# Sheet_Power.net
KiCad netlist of a schematic drawn in Altium Designer
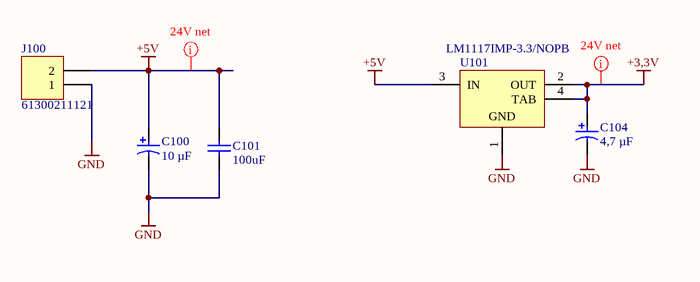
[diagram p0: Sheet_Power.SchDoc]

(export (version "E")
  (design (tool "Eeschema 10.0.6"))
  (components
    (comp (ref "C100")
      (value "10 µF")
      (footprint "KEMT-520-D_Low")
      (description "10 µF, 35V, 125 mOhm, Gr. D\npartnumb: T495D106K035ATE125")
      (fields (field (name "MANUFACTURER") "KEMET") (field (name "TOLERANCE") "±10%"))
      (libsource (lib "Altium Vault EMBL") (part "CMP-001-0033-3"))
    )
    (comp (ref "C101")
      (value "100uF")
      (footprint "CAPC1206(3216)190_L")
      (description "CAP 100uF 6.3V ±20% 1206 (3216 Metric) Thickness 1.9mm SMD")
      (fields (field (name "TOLERANCE") "Â±20%") (field (name "PARTNUMBER") "885012108005"))
      (libsource (lib "Altium Vault EMBL 3") (part "CMP-00469-2"))
    )
    (comp (ref "C104")
      (value "4,7 µF")
      (footprint "A Package")
      (description "4,7 µF; 6V; Gr. A; T491A475K006AT")
      (fields (field (name "MANUFACTURER") "KEMET") (field (name "TOLERANCE") "±10%"))
      (libsource (lib "Altium Vault EMBL") (part "CMP-001-0039-3"))
    )
    (comp (ref "J100")
      (value "61300211121")
      (footprint "61300211121")
      (description "2Pol; gerade; WR-PHD 2.54 mm THT Pin Header")
      (fields (field (name "MANUFACTURER") "Wurth Electronics"))
      (libsource (lib "Altium Vault EMBL") (part "CMP-001-0071-1"))
    )
    (comp (ref "U101")
      (value "LM1117IMP-3.3/NOPB")
      (footprint "DCY0004A_N")
      (description "800mA Low-Dropout Linear Regulator, 4-pin SOT-223, Pb-Free")
      (fields (field (name "MANUFACTURER") "Texas Instruments"))
      (libsource (lib "Altium Vault EMBL") (part "CMP-00484-1"))
    )
  )
  (nets
    (net (code "1") (name "+3,3V") (class "Default")
      (node (ref "C104") (pin "1") (pinfunction "1_1") (pintype "passive"))
      (node (ref "U101") (pin "2") (pinfunction "OUT_2") (pintype "power_in"))
      (node (ref "U101") (pin "4") (pinfunction "TAB_4") (pintype "power_in"))
    )
    (net (code "2") (name "+5V") (class "Default")
      (node (ref "C100") (pin "1") (pinfunction "1_1") (pintype "passive"))
      (node (ref "C101") (pin "2") (pinfunction "2_2") (pintype "passive"))
      (node (ref "J100") (pin "2") (pinfunction "2_2") (pintype "passive"))
      (node (ref "U101") (pin "3") (pinfunction "IN_3") (pintype "power_in"))
    )
    (net (code "3") (name "GND") (class "Default")
      (node (ref "C100") (pin "2") (pinfunction "2_2") (pintype "passive"))
      (node (ref "C101") (pin "1") (pinfunction "1_1") (pintype "passive"))
      (node (ref "C104") (pin "2") (pinfunction "2_2") (pintype "passive"))
      (node (ref "J100") (pin "1") (pinfunction "1_1") (pintype "passive"))
      (node (ref "U101") (pin "1") (pinfunction "GND_1") (pintype "power_in"))
    )
  )
)
